# V1.net
KiCad netlist of a schematic drawn in Altium Designer
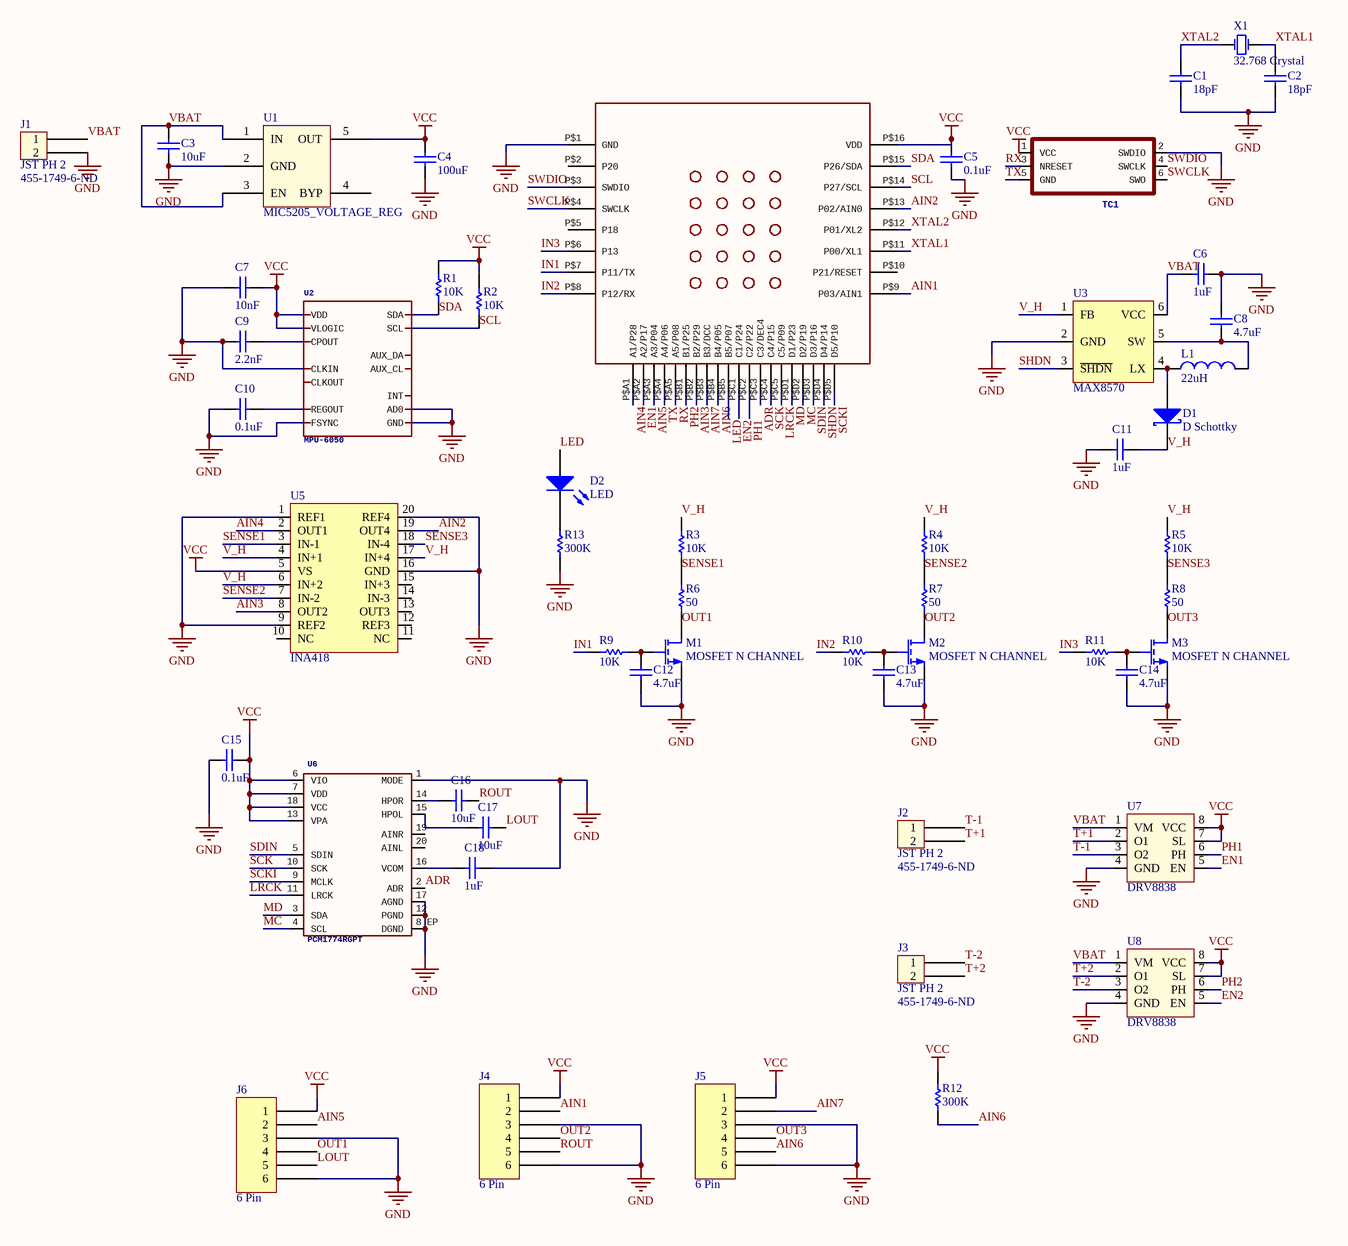
[diagram p0: V1.SchDoc]

(export (version "E")
  (design (tool "Eeschema 10.0.6"))
  (components
    (comp (ref "C1")
      (value "18pF")
      (footprint "0603W")
      (description "SMD Cap 0603")
      (libsource (lib "Artem_Library") (part "Capacitor"))
    )
    (comp (ref "C2")
      (value "18pF")
      (footprint "0603W")
      (description "SMD Cap 0603")
      (libsource (lib "Artem_Library") (part "Capacitor"))
    )
    (comp (ref "C3")
      (value "10uF")
      (footprint "0603W")
      (description "SMD Cap 0603")
      (libsource (lib "Artem_Library") (part "Capacitor"))
    )
    (comp (ref "C4")
      (value "100uF")
      (footprint "0603W")
      (description "SMD Cap 0603")
      (libsource (lib "Artem_Library") (part "Capacitor"))
    )
    (comp (ref "C5")
      (value "0.1uF")
      (footprint "0603W")
      (description "SMD Cap 0603")
      (libsource (lib "Artem_Library") (part "Capacitor"))
    )
    (comp (ref "C6")
      (value "1uF")
      (footprint "0603W")
      (description "SMD Cap 0603")
      (libsource (lib "Artem_Library") (part "Capacitor"))
    )
    (comp (ref "C7")
      (value "10nF")
      (footprint "0603W")
      (description "SMD Cap 0603")
      (libsource (lib "Artem_Library") (part "Capacitor"))
    )
    (comp (ref "C8")
      (value "4.7uF")
      (footprint "0603W")
      (description "SMD Cap 0603")
      (libsource (lib "Artem_Library") (part "Capacitor"))
    )
    (comp (ref "C9")
      (value "2.2nF")
      (footprint "0603W")
      (description "SMD Cap 0603")
      (libsource (lib "Artem_Library") (part "Capacitor"))
    )
    (comp (ref "C10")
      (value "0.1uF")
      (footprint "0603W")
      (description "SMD Cap 0603")
      (libsource (lib "Artem_Library") (part "Capacitor"))
    )
    (comp (ref "C11")
      (value "1uF")
      (footprint "0603W")
      (description "SMD Cap 0603")
      (libsource (lib "Artem_Library") (part "Capacitor"))
    )
    (comp (ref "C12")
      (value "4.7uF")
      (footprint "0603W")
      (description "SMD Cap 0603")
      (libsource (lib "Artem_Library") (part "Capacitor"))
    )
    (comp (ref "C13")
      (value "4.7uF")
      (footprint "0603W")
      (description "SMD Cap 0603")
      (libsource (lib "Artem_Library") (part "Capacitor"))
    )
    (comp (ref "C14")
      (value "4.7uF")
      (footprint "0603W")
      (description "SMD Cap 0603")
      (libsource (lib "Artem_Library") (part "Capacitor"))
    )
    (comp (ref "C15")
      (value "0.1uF")
      (footprint "0603W")
      (description "SMD Cap 0603")
      (libsource (lib "Artem_Library") (part "Capacitor"))
    )
    (comp (ref "C16")
      (value "10uF")
      (footprint "0603W")
      (description "SMD Cap 0603")
      (libsource (lib "Artem_Library") (part "Capacitor"))
    )
    (comp (ref "C17")
      (value "10uF")
      (footprint "0603W")
      (description "SMD Cap 0603")
      (libsource (lib "Artem_Library") (part "Capacitor"))
    )
    (comp (ref "C18")
      (value "1uF")
      (footprint "0603W")
      (description "SMD Cap 0603")
      (libsource (lib "Artem_Library") (part "Capacitor"))
    )
    (comp (ref "D1")
      (value "D Schottky")
      (footprint "0603W")
      (description "Schottky Diode")
      (fields (field (name "PUBLISHER") "Altium Limited"))
      (libsource (lib "Miscellaneous Devices") (part "D Schottky"))
    )
    (comp (ref "D2")
      (value "LED")
      (footprint "0603 LED")
      (description "LED SMD 1206/0603")
      (libsource (lib "Artem_Library") (part "LED"))
    )
    (comp (ref "J1")
      (value "JST PH 2")
      (footprint "JST PH 2")
      (fields (field (name "SUPPLIER PART NUMBER 1") "455-1749-6-ND"))
      (libsource (lib "Artem_Library") (part "JST PH 2"))
    )
    (comp (ref "J2")
      (value "JST PH 2")
      (footprint "JST PH 2")
      (fields (field (name "SUPPLIER PART NUMBER 1") "455-1749-6-ND"))
      (libsource (lib "Artem_Library") (part "JST PH 2"))
    )
    (comp (ref "J3")
      (value "JST PH 2")
      (footprint "JST PH 2")
      (fields (field (name "SUPPLIER PART NUMBER 1") "455-1749-6-ND"))
      (libsource (lib "Artem_Library") (part "JST PH 2"))
    )
    (comp (ref "J4")
      (value "6 Pin")
      (footprint "JST SM06B-SRSS-TB")
      (libsource (lib "Connectors") (part "6 Pin"))
    )
    (comp (ref "J5")
      (value "6 Pin")
      (footprint "JST SM06B-SRSS-TB")
      (libsource (lib "Connectors") (part "6 Pin"))
    )
    (comp (ref "J6")
      (value "6 Pin")
      (footprint "JST SM06B-SRSS-TB")
      (libsource (lib "Connectors") (part "6 Pin"))
    )
    (comp (ref "L1") (value "22uH") (footprint "0603W") (libsource (lib "Artem_Library") (part "Inductor")))
    (comp (ref "M1")
      (value "MOSFET N CHANNEL")
      (footprint "SOT323")
      (fields (field (name "DIGIKEY PART NUMBER") "568-5987-1-ND"))
      (libsource (lib "Artem_Library") (part "MOSFET N CHANNEL"))
    )
    (comp (ref "M2")
      (value "MOSFET N CHANNEL")
      (footprint "SOT323")
      (fields (field (name "DIGIKEY PART NUMBER") "568-5987-1-ND"))
      (libsource (lib "Artem_Library") (part "MOSFET N CHANNEL"))
    )
    (comp (ref "M3")
      (value "MOSFET N CHANNEL")
      (footprint "SOT323")
      (fields (field (name "DIGIKEY PART NUMBER") "568-5987-1-ND"))
      (libsource (lib "Artem_Library") (part "MOSFET N CHANNEL"))
    )
    (comp (ref "R1") (value "10K") (footprint "0603W") (libsource (lib "Artem_Library") (part "Resistor")))
    (comp (ref "R2") (value "10K") (footprint "0603W") (libsource (lib "Artem_Library") (part "Resistor")))
    (comp (ref "R3") (value "10K") (footprint "0603W") (libsource (lib "Artem_Library") (part "Resistor")))
    (comp (ref "R4") (value "10K") (footprint "0603W") (libsource (lib "Artem_Library") (part "Resistor")))
    (comp (ref "R5") (value "10K") (footprint "0603W") (libsource (lib "Artem_Library") (part "Resistor")))
    (comp (ref "R6") (value "50") (footprint "0603W") (libsource (lib "Artem_Library") (part "Resistor")))
    (comp (ref "R7") (value "50") (footprint "0603W") (libsource (lib "Artem_Library") (part "Resistor")))
    (comp (ref "R8") (value "50") (footprint "0603W") (libsource (lib "Artem_Library") (part "Resistor")))
    (comp (ref "R9") (value "10K") (footprint "0603W") (libsource (lib "Artem_Library") (part "Resistor")))
    (comp (ref "R10") (value "10K") (footprint "0603W") (libsource (lib "Artem_Library") (part "Resistor")))
    (comp (ref "R11") (value "10K") (footprint "0603W") (libsource (lib "Artem_Library") (part "Resistor")))
    (comp (ref "R12") (value "300K") (footprint "0603W") (libsource (lib "Artem_Library") (part "Resistor")))
    (comp (ref "R13") (value "300K") (footprint "0603W") (libsource (lib "Artem_Library") (part "Resistor")))
    (comp (ref "TC1")
      (value "~")
      (footprint "TC2030-IDC-NL")
      (libsource (lib "TagConnect") (part "TC2030-IDC-NL"))
    )
    (comp (ref "U1")
      (value "MIC5205_VOLTAGE_REG")
      (footprint "SOT-23-5")
      (description "3.3V LDO SMD")
      (libsource (lib "Artem_Library") (part "MIC5205_VOLTAGE_REG"))
    )
    (comp (ref "U2")
      (value "MPU-6050")
      (footprint "QFN24")
      (fields (field (name "LIBRARYNAME") "invensense"))
      (libsource (lib "invensense") (part "MPU-6050"))
    )
    (comp (ref "U3") (value "MAX8570") (footprint "SOT23-6") (libsource (lib "aby") (part "MAX8570")))
    (comp (ref "U4")
      (value "B3 DCC ,C3 DEC4 for power saving , 10uH , 15nH")
      (footprint "BC832")
      (libsource (lib "BC832") (part "BC832-V1"))
    )
    (comp (ref "U5") (value "INA418") (footprint "TSSOP-20") (libsource (lib "aby") (part "INA418")))
    (comp (ref "U6") (value "PCM1774RGPT") (footprint "QFN20") (libsource (lib "TI") (part "PCM1774RGPT")))
    (comp (ref "U7") (value "DRV8838") (footprint "DRV8838") (libsource (lib "aby") (part "DRV8838")))
    (comp (ref "U8") (value "DRV8838") (footprint "DRV8838") (libsource (lib "aby") (part "DRV8838")))
    (comp (ref "X1")
      (value "32.768 Crystal")
      (footprint "32.768 Crystal")
      (libsource (lib "Artem_Library") (part "32.768 Crystal"))
    )
  )
  (nets
    (net (code "1") (name "/ADR") (class "Default")
      (node (ref "U4") (pin "P$C3") (pinfunction "C3/DEC4_P$C3") (pintype "passive"))
      (node (ref "U6") (pin "2") (pinfunction "ADR_2") (pintype "passive"))
    )
    (net (code "2") (name "/AIN1") (class "Default")
      (node (ref "J4") (pin "2") (pinfunction "2_2") (pintype "passive"))
      (node (ref "U4") (pin "P$9") (pinfunction "P03/AIN1_P$9") (pintype "passive"))
    )
    (net (code "3") (name "/AIN2") (class "Default")
      (node (ref "U4") (pin "P$13") (pinfunction "P02/AIN0_P$13") (pintype "passive"))
      (node (ref "U5") (pin "19") (pinfunction "OUT4_19") (pintype "passive"))
    )
    (net (code "4") (name "/AIN3") (class "Default")
      (node (ref "U4") (pin "P$B2") (pinfunction "B2/P29_P$B2") (pintype "passive"))
      (node (ref "U5") (pin "8") (pinfunction "OUT2_8") (pintype "passive"))
    )
    (net (code "5") (name "/AIN4") (class "Default")
      (node (ref "U4") (pin "P$A1") (pinfunction "A1/P28_P$A1") (pintype "passive"))
      (node (ref "U5") (pin "2") (pinfunction "OUT1_2") (pintype "passive"))
    )
    (net (code "6") (name "/AIN5") (class "Default")
      (node (ref "J6") (pin "2") (pinfunction "2_2") (pintype "passive"))
      (node (ref "U4") (pin "P$A3") (pinfunction "A3/P04_P$A3") (pintype "passive"))
    )
    (net (code "7") (name "/AIN6") (class "Default")
      (node (ref "J5") (pin "5") (pinfunction "5_5") (pintype "passive"))
      (node (ref "R12") (pin "1") (pinfunction "1_1") (pintype "passive"))
      (node (ref "U4") (pin "P$B4") (pinfunction "B4/P05_P$B4") (pintype "passive"))
    )
    (net (code "8") (name "/AIN7") (class "Default")
      (node (ref "J5") (pin "2") (pinfunction "2_2") (pintype "passive"))
      (node (ref "U4") (pin "P$B3") (pinfunction "B3/DCC_P$B3") (pintype "passive"))
    )
    (net (code "9") (name "/EN1") (class "Default")
      (node (ref "U4") (pin "P$A2") (pinfunction "A2/P17_P$A2") (pintype "passive"))
      (node (ref "U7") (pin "5") (pinfunction "EN_5") (pintype "passive"))
    )
    (net (code "10") (name "/EN2") (class "Default")
      (node (ref "U4") (pin "P$C1") (pinfunction "C1/P24_P$C1") (pintype "passive"))
      (node (ref "U8") (pin "5") (pinfunction "EN_5") (pintype "passive"))
    )
    (net (code "11") (name "/IN1") (class "Default")
      (node (ref "R9") (pin "1") (pinfunction "1_1") (pintype "passive"))
      (node (ref "U4") (pin "P$7") (pinfunction "P11/TX_P$7") (pintype "passive"))
    )
    (net (code "12") (name "/IN2") (class "Default")
      (node (ref "R10") (pin "1") (pinfunction "1_1") (pintype "passive"))
      (node (ref "U4") (pin "P$8") (pinfunction "P12/RX_P$8") (pintype "passive"))
    )
    (net (code "13") (name "/IN3") (class "Default")
      (node (ref "R11") (pin "1") (pinfunction "1_1") (pintype "passive"))
      (node (ref "U4") (pin "P$6") (pinfunction "P13_P$6") (pintype "passive"))
    )
    (net (code "14") (name "/LED") (class "Default")
      (node (ref "D2") (pin "1") (pinfunction "A_1") (pintype "passive"))
      (node (ref "U4") (pin "P$B5") (pinfunction "B5/P07_P$B5") (pintype "passive"))
    )
    (net (code "15") (name "/LOUT") (class "Default")
      (node (ref "C17") (pin "1") (pinfunction "1_1") (pintype "passive"))
      (node (ref "J6") (pin "5") (pinfunction "5_5") (pintype "passive"))
    )
    (net (code "16") (name "/LRCK") (class "Default")
      (node (ref "U4") (pin "P$C5") (pinfunction "C5/P09_P$C5") (pintype "passive"))
      (node (ref "U6") (pin "11") (pinfunction "LRCK_11") (pintype "passive"))
    )
    (net (code "17") (name "/MC") (class "Default")
      (node (ref "U4") (pin "P$D2") (pinfunction "D2/P19_P$D2") (pintype "passive"))
      (node (ref "U6") (pin "4") (pinfunction "SCL_4") (pintype "passive"))
    )
    (net (code "18") (name "/MD") (class "Default")
      (node (ref "U4") (pin "P$D1") (pinfunction "D1/P23_P$D1") (pintype "passive"))
      (node (ref "U6") (pin "3") (pinfunction "SDA_3") (pintype "passive"))
    )
    (net (code "19") (name "/OUT1") (class "Default")
      (node (ref "J6") (pin "4") (pinfunction "4_4") (pintype "passive"))
      (node (ref "M1") (pin "3") (pinfunction "D_3") (pintype "passive"))
      (node (ref "R6") (pin "1") (pinfunction "1_1") (pintype "passive"))
    )
    (net (code "20") (name "/OUT2") (class "Default")
      (node (ref "J4") (pin "4") (pinfunction "4_4") (pintype "passive"))
      (node (ref "M2") (pin "3") (pinfunction "D_3") (pintype "passive"))
      (node (ref "R7") (pin "1") (pinfunction "1_1") (pintype "passive"))
    )
    (net (code "21") (name "/OUT3") (class "Default")
      (node (ref "J5") (pin "4") (pinfunction "4_4") (pintype "passive"))
      (node (ref "M3") (pin "3") (pinfunction "D_3") (pintype "passive"))
      (node (ref "R8") (pin "1") (pinfunction "1_1") (pintype "passive"))
    )
    (net (code "22") (name "/PH1") (class "Default")
      (node (ref "U4") (pin "P$C2") (pinfunction "C2/P22_P$C2") (pintype "passive"))
      (node (ref "U7") (pin "6") (pinfunction "PH_6") (pintype "passive"))
    )
    (net (code "23") (name "/PH2") (class "Default")
      (node (ref "U4") (pin "P$B1") (pinfunction "B1/P25_P$B1") (pintype "passive"))
      (node (ref "U8") (pin "6") (pinfunction "PH_6") (pintype "passive"))
    )
    (net (code "24") (name "/ROUT") (class "Default")
      (node (ref "C16") (pin "1") (pinfunction "1_1") (pintype "passive"))
      (node (ref "J4") (pin "5") (pinfunction "5_5") (pintype "passive"))
    )
    (net (code "25") (name "/RX") (class "Default")
      (node (ref "TC1") (pin "3") (pinfunction "NRESET_3") (pintype "passive"))
      (node (ref "U4") (pin "P$A5") (pinfunction "A5/P08_P$A5") (pintype "passive"))
    )
    (net (code "26") (name "/SCK") (class "Default")
      (node (ref "U4") (pin "P$C4") (pinfunction "C4/P15_P$C4") (pintype "passive"))
      (node (ref "U6") (pin "10") (pinfunction "SCK_10") (pintype "passive"))
    )
    (net (code "27") (name "/SCKI") (class "Default")
      (node (ref "U4") (pin "P$D5") (pinfunction "D5/P10_P$D5") (pintype "passive"))
      (node (ref "U6") (pin "9") (pinfunction "MCLK_9") (pintype "passive"))
    )
    (net (code "28") (name "/SCL") (class "Default")
      (node (ref "R2") (pin "2") (pinfunction "2_2") (pintype "passive"))
      (node (ref "U2") (pin "23") (pinfunction "SCL_23") (pintype "passive"))
      (node (ref "U4") (pin "P$14") (pinfunction "P27/SCL_P$14") (pintype "passive"))
    )
    (net (code "29") (name "/SDA") (class "Default")
      (node (ref "R1") (pin "2") (pinfunction "2_2") (pintype "passive"))
      (node (ref "U2") (pin "24") (pinfunction "SDA_24") (pintype "passive"))
      (node (ref "U4") (pin "P$15") (pinfunction "P26/SDA_P$15") (pintype "passive"))
    )
    (net (code "30") (name "/SDIN") (class "Default")
      (node (ref "U4") (pin "P$D3") (pinfunction "D3/P16_P$D3") (pintype "passive"))
      (node (ref "U6") (pin "5") (pinfunction "SDIN_5") (pintype "passive"))
    )
    (net (code "31") (name "/SENSE1") (class "Default")
      (node (ref "R3") (pin "1") (pinfunction "1_1") (pintype "passive"))
      (node (ref "R6") (pin "2") (pinfunction "2_2") (pintype "passive"))
      (node (ref "U5") (pin "3") (pinfunction "IN-1_3") (pintype "passive"))
    )
    (net (code "32") (name "/SENSE2") (class "Default")
      (node (ref "R4") (pin "1") (pinfunction "1_1") (pintype "passive"))
      (node (ref "R7") (pin "2") (pinfunction "2_2") (pintype "passive"))
      (node (ref "U5") (pin "7") (pinfunction "IN-2_7") (pintype "passive"))
    )
    (net (code "33") (name "/SENSE3") (class "Default")
      (node (ref "R5") (pin "1") (pinfunction "1_1") (pintype "passive"))
      (node (ref "R8") (pin "2") (pinfunction "2_2") (pintype "passive"))
      (node (ref "U5") (pin "18") (pinfunction "IN-4_18") (pintype "passive"))
    )
    (net (code "34") (name "/SHDN") (class "Default")
      (node (ref "U3") (pin "3") (pinfunction "~{SHDN}_3") (pintype "passive"))
      (node (ref "U4") (pin "P$D4") (pinfunction "D4/P14_P$D4") (pintype "passive"))
    )
    (net (code "35") (name "/SWCLK") (class "Default")
      (node (ref "TC1") (pin "6") (pinfunction "SWO_6") (pintype "passive"))
      (node (ref "U4") (pin "P$4") (pinfunction "SWCLK_P$4") (pintype "passive"))
    )
    (net (code "36") (name "/SWDIO") (class "Default")
      (node (ref "TC1") (pin "4") (pinfunction "SWCLK_4") (pintype "passive"))
      (node (ref "U4") (pin "P$3") (pinfunction "SWDIO_P$3") (pintype "passive"))
    )
    (net (code "37") (name "/T+1") (class "Default")
      (node (ref "J2") (pin "2") (pinfunction "2_2") (pintype "passive"))
      (node (ref "U7") (pin "2") (pinfunction "O1_2") (pintype "passive"))
    )
    (net (code "38") (name "/T+2") (class "Default")
      (node (ref "J3") (pin "2") (pinfunction "2_2") (pintype "passive"))
      (node (ref "U8") (pin "2") (pinfunction "O1_2") (pintype "passive"))
    )
    (net (code "39") (name "/T-1") (class "Default")
      (node (ref "J2") (pin "1") (pinfunction "1_1") (pintype "passive"))
      (node (ref "U7") (pin "3") (pinfunction "O2_3") (pintype "passive"))
    )
    (net (code "40") (name "/T-2") (class "Default")
      (node (ref "J3") (pin "1") (pinfunction "1_1") (pintype "passive"))
      (node (ref "U8") (pin "3") (pinfunction "O2_3") (pintype "passive"))
    )
    (net (code "41") (name "/TX") (class "Default")
      (node (ref "TC1") (pin "5") (pinfunction "GND_5") (pintype "passive"))
      (node (ref "U4") (pin "P$A4") (pinfunction "A4/P06_P$A4") (pintype "passive"))
    )
    (net (code "42") (name "/VBAT") (class "Default")
      (node (ref "C3") (pin "2") (pinfunction "2_2") (pintype "passive"))
      (node (ref "C6") (pin "2") (pinfunction "2_2") (pintype "passive"))
      (node (ref "J1") (pin "1") (pinfunction "1_1") (pintype "passive"))
      (node (ref "U1") (pin "1") (pinfunction "IN_1") (pintype "passive"))
      (node (ref "U1") (pin "3") (pinfunction "EN_3") (pintype "passive"))
      (node (ref "U3") (pin "6") (pinfunction "VCC_6") (pintype "passive"))
      (node (ref "U7") (pin "1") (pinfunction "VM_1") (pintype "passive"))
      (node (ref "U8") (pin "1") (pinfunction "VM_1") (pintype "passive"))
    )
    (net (code "43") (name "/V_H") (class "Default")
      (node (ref "C11") (pin "1") (pinfunction "1_1") (pintype "passive"))
      (node (ref "D1") (pin "2") (pinfunction "K_2") (pintype "passive"))
      (node (ref "R3") (pin "2") (pinfunction "2_2") (pintype "passive"))
      (node (ref "R4") (pin "2") (pinfunction "2_2") (pintype "passive"))
      (node (ref "R5") (pin "2") (pinfunction "2_2") (pintype "passive"))
      (node (ref "U3") (pin "1") (pinfunction "FB_1") (pintype "passive"))
      (node (ref "U5") (pin "17") (pinfunction "IN+4_17") (pintype "passive"))
      (node (ref "U5") (pin "4") (pinfunction "IN+1_4") (pintype "passive"))
      (node (ref "U5") (pin "6") (pinfunction "IN+2_6") (pintype "passive"))
    )
    (net (code "44") (name "/XTAL1") (class "Default")
      (node (ref "C2") (pin "2") (pinfunction "2_2") (pintype "passive"))
      (node (ref "U4") (pin "P$11") (pinfunction "P00/XL1_P$11") (pintype "passive"))
      (node (ref "X1") (pin "2") (pinfunction "2_2") (pintype "passive"))
    )
    (net (code "45") (name "/XTAL2") (class "Default")
      (node (ref "C1") (pin "1") (pinfunction "1_1") (pintype "passive"))
      (node (ref "U4") (pin "P$12") (pinfunction "P01/XL2_P$12") (pintype "passive"))
      (node (ref "X1") (pin "1") (pinfunction "1_1") (pintype "passive"))
    )
    (net (code "46") (name "GND") (class "Default")
      (node (ref "C1") (pin "2") (pinfunction "2_2") (pintype "passive"))
      (node (ref "C10") (pin "2") (pinfunction "2_2") (pintype "passive"))
      (node (ref "C11") (pin "2") (pinfunction "2_2") (pintype "passive"))
      (node (ref "C12") (pin "2") (pinfunction "2_2") (pintype "passive"))
      (node (ref "C13") (pin "2") (pinfunction "2_2") (pintype "passive"))
      (node (ref "C14") (pin "2") (pinfunction "2_2") (pintype "passive"))
      (node (ref "C15") (pin "2") (pinfunction "2_2") (pintype "passive"))
      (node (ref "C18") (pin "1") (pinfunction "1_1") (pintype "passive"))
      (node (ref "C2") (pin "1") (pinfunction "1_1") (pintype "passive"))
      (node (ref "C3") (pin "1") (pinfunction "1_1") (pintype "passive"))
      (node (ref "C4") (pin "1") (pinfunction "1_1") (pintype "passive"))
      (node (ref "C5") (pin "1") (pinfunction "1_1") (pintype "passive"))
      (node (ref "C6") (pin "1") (pinfunction "1_1") (pintype "passive"))
      (node (ref "C7") (pin "2") (pinfunction "2_2") (pintype "passive"))
      (node (ref "C8") (pin "1") (pinfunction "1_1") (pintype "passive"))
      (node (ref "C9") (pin "2") (pinfunction "2_2") (pintype "passive"))
      (node (ref "J1") (pin "2") (pinfunction "2_2") (pintype "passive"))
      (node (ref "J4") (pin "3") (pinfunction "3_3") (pintype "passive"))
      (node (ref "J4") (pin "6") (pinfunction "6_6") (pintype "passive"))
      (node (ref "J5") (pin "3") (pinfunction "3_3") (pintype "passive"))
      (node (ref "J5") (pin "6") (pinfunction "6_6") (pintype "passive"))
      (node (ref "J6") (pin "3") (pinfunction "3_3") (pintype "passive"))
      (node (ref "J6") (pin "6") (pinfunction "6_6") (pintype "passive"))
      (node (ref "M1") (pin "2") (pinfunction "S_2") (pintype "passive"))
      (node (ref "M2") (pin "2") (pinfunction "S_2") (pintype "passive"))
      (node (ref "M3") (pin "2") (pinfunction "S_2") (pintype "passive"))
      (node (ref "R13") (pin "1") (pinfunction "1_1") (pintype "passive"))
      (node (ref "TC1") (pin "2") (pinfunction "SWDIO_2") (pintype "passive"))
      (node (ref "U1") (pin "2") (pinfunction "GND_2") (pintype "passive"))
      (node (ref "U2") (pin "1") (pinfunction "CLKIN_1") (pintype "passive"))
      (node (ref "U2") (pin "11") (pinfunction "FSYNC_11") (pintype "passive"))
      (node (ref "U2") (pin "18") (pinfunction "GND_18") (pintype "passive"))
      (node (ref "U2") (pin "9") (pinfunction "AD0_9") (pintype "passive"))
      (node (ref "U3") (pin "2") (pinfunction "GND_2") (pintype "passive"))
      (node (ref "U4") (pin "P$1") (pinfunction "GND_P$1") (pintype "passive"))
      (node (ref "U5") (pin "1") (pinfunction "REF1_1") (pintype "passive"))
      (node (ref "U5") (pin "16") (pinfunction "GND_16") (pintype "passive"))
      (node (ref "U5") (pin "20") (pinfunction "REF4_20") (pintype "passive"))
      (node (ref "U5") (pin "9") (pinfunction "REF2_9") (pintype "passive"))
      (node (ref "U6") (pin "1") (pinfunction "MODE_1") (pintype "passive"))
      (node (ref "U6") (pin "12") (pinfunction "PGND_12") (pintype "passive"))
      (node (ref "U6") (pin "17") (pinfunction "AGND_17") (pintype "passive"))
      (node (ref "U6") (pin "8_EP") (pinfunction "DGND_8_EP") (pintype "passive"))
      (node (ref "U7") (pin "4") (pinfunction "GND_4") (pintype "passive"))
      (node (ref "U8") (pin "4") (pinfunction "GND_4") (pintype "passive"))
    )
    (net (code "47") (name "Net-(D1-A)") (class "Default")
      (node (ref "D1") (pin "1") (pinfunction "A_1") (pintype "passive"))
      (node (ref "L1") (pin "1") (pinfunction "1_1") (pintype "passive"))
      (node (ref "U3") (pin "4") (pinfunction "LX_4") (pintype "passive"))
    )
    (net (code "48") (name "Net-(D2-K)") (class "Default")
      (node (ref "D2") (pin "2") (pinfunction "K_2") (pintype "passive"))
      (node (ref "R13") (pin "2") (pinfunction "2_2") (pintype "passive"))
    )
    (net (code "49") (name "Net-(M1-G)") (class "Default")
      (node (ref "C12") (pin "1") (pinfunction "1_1") (pintype "passive"))
      (node (ref "M1") (pin "1") (pinfunction "G_1") (pintype "passive"))
      (node (ref "R9") (pin "2") (pinfunction "2_2") (pintype "passive"))
    )
    (net (code "50") (name "Net-(M2-G)") (class "Default")
      (node (ref "C13") (pin "1") (pinfunction "1_1") (pintype "passive"))
      (node (ref "M2") (pin "1") (pinfunction "G_1") (pintype "passive"))
      (node (ref "R10") (pin "2") (pinfunction "2_2") (pintype "passive"))
    )
    (net (code "51") (name "Net-(M3-G)") (class "Default")
      (node (ref "C14") (pin "1") (pinfunction "1_1") (pintype "passive"))
      (node (ref "M3") (pin "1") (pinfunction "G_1") (pintype "passive"))
      (node (ref "R11") (pin "2") (pinfunction "2_2") (pintype "passive"))
    )
    (net (code "52") (name "Net-(U2-CPOUT)") (class "Default")
      (node (ref "C9") (pin "1") (pinfunction "1_1") (pintype "passive"))
      (node (ref "U2") (pin "20") (pinfunction "CPOUT_20") (pintype "passive"))
    )
    (net (code "53") (name "Net-(U2-REGOUT)") (class "Default")
      (node (ref "C10") (pin "1") (pinfunction "1_1") (pintype "passive"))
      (node (ref "U2") (pin "10") (pinfunction "REGOUT_10") (pintype "passive"))
    )
    (net (code "54") (name "Net-(U3-SW)") (class "Default")
      (node (ref "C8") (pin "2") (pinfunction "2_2") (pintype "passive"))
      (node (ref "L1") (pin "2") (pinfunction "2_2") (pintype "passive"))
      (node (ref "U3") (pin "5") (pinfunction "SW_5") (pintype "passive"))
    )
    (net (code "55") (name "Net-(U6-HPOL)") (class "Default")
      (node (ref "C17") (pin "2") (pinfunction "2_2") (pintype "passive"))
      (node (ref "U6") (pin "15") (pinfunction "HPOL_15") (pintype "passive"))
    )
    (net (code "56") (name "Net-(U6-HPOR)") (class "Default")
      (node (ref "C16") (pin "2") (pinfunction "2_2") (pintype "passive"))
      (node (ref "U6") (pin "14") (pinfunction "HPOR_14") (pintype "passive"))
    )
    (net (code "57") (name "Net-(U6-VCOM)") (class "Default")
      (node (ref "C18") (pin "2") (pinfunction "2_2") (pintype "passive"))
      (node (ref "U6") (pin "16") (pinfunction "VCOM_16") (pintype "passive"))
    )
    (net (code "58") (name "VCC") (class "Default")
      (node (ref "C15") (pin "1") (pinfunction "1_1") (pintype "passive"))
      (node (ref "C4") (pin "2") (pinfunction "2_2") (pintype "passive"))
      (node (ref "C5") (pin "2") (pinfunction "2_2") (pintype "passive"))
      (node (ref "C7") (pin "1") (pinfunction "1_1") (pintype "passive"))
      (node (ref "J4") (pin "1") (pinfunction "1_1") (pintype "passive"))
      (node (ref "J5") (pin "1") (pinfunction "1_1") (pintype "passive"))
      (node (ref "J6") (pin "1") (pinfunction "1_1") (pintype "passive"))
      (node (ref "R1") (pin "1") (pinfunction "1_1") (pintype "passive"))
      (node (ref "R12") (pin "2") (pinfunction "2_2") (pintype "passive"))
      (node (ref "R2") (pin "1") (pinfunction "1_1") (pintype "passive"))
      (node (ref "TC1") (pin "1") (pinfunction "VCC_1") (pintype "passive"))
      (node (ref "U1") (pin "5") (pinfunction "OUT_5") (pintype "passive"))
      (node (ref "U2") (pin "13") (pinfunction "VDD_13") (pintype "passive"))
      (node (ref "U2") (pin "8") (pinfunction "VLOGIC_8") (pintype "passive"))
      (node (ref "U4") (pin "P$16") (pinfunction "VDD_P$16") (pintype "passive"))
      (node (ref "U5") (pin "5") (pinfunction "VS_5") (pintype "passive"))
      (node (ref "U6") (pin "13") (pinfunction "VPA_13") (pintype "passive"))
      (node (ref "U6") (pin "18") (pinfunction "VCC_18") (pintype "passive"))
      (node (ref "U6") (pin "6") (pinfunction "VIO_6") (pintype "passive"))
      (node (ref "U6") (pin "7") (pinfunction "VDD_7") (pintype "passive"))
      (node (ref "U7") (pin "7") (pinfunction "SL_7") (pintype "passive"))
      (node (ref "U7") (pin "8") (pinfunction "VCC_8") (pintype "passive"))
      (node (ref "U8") (pin "7") (pinfunction "SL_7") (pintype "passive"))
      (node (ref "U8") (pin "8") (pinfunction "VCC_8") (pintype "passive"))
    )
    (net (code "59") (name "unconnected-(U1-BYP-Pad4)") (class "Default")
      (node (ref "U1") (pin "4") (pinfunction "BYP_4") (pintype "passive"))
    )
    (net (code "60") (name "unconnected-(U2-AUX_CL-Pad7)") (class "Default")
      (node (ref "U2") (pin "7") (pinfunction "AUX_CL_7") (pintype "passive"))
    )
    (net (code "61") (name "unconnected-(U2-AUX_DA-Pad6)") (class "Default")
      (node (ref "U2") (pin "6") (pinfunction "AUX_DA_6") (pintype "passive"))
    )
    (net (code "62") (name "unconnected-(U2-CLKOUT-Pad22)") (class "Default")
      (node (ref "U2") (pin "22") (pinfunction "CLKOUT_22") (pintype "passive"))
    )
    (net (code "63") (name "unconnected-(U2-INT-Pad12)") (class "Default")
      (node (ref "U2") (pin "12") (pinfunction "INT_12") (pintype "passive"))
    )
    (net (code "64") (name "unconnected-(U4-P18-PadP$5)") (class "Default")
      (node (ref "U4") (pin "P$5") (pinfunction "P18_P$5") (pintype "passive"))
    )
    (net (code "65") (name "unconnected-(U4-P20-PadP$2)") (class "Default")
      (node (ref "U4") (pin "P$2") (pinfunction "P20_P$2") (pintype "passive"))
    )
    (net (code "66") (name "unconnected-(U4-P21{slash}RESET-PadP$10)") (class "Default")
      (node (ref "U4") (pin "P$10") (pinfunction "P21/RESET_P$10") (pintype "passive"))
    )
    (net (code "67") (name "unconnected-(U5-IN+3-Pad15)") (class "Default")
      (node (ref "U5") (pin "15") (pinfunction "IN+3_15") (pintype "passive"))
    )
    (net (code "68") (name "unconnected-(U5-IN-3-Pad14)") (class "Default")
      (node (ref "U5") (pin "14") (pinfunction "IN-3_14") (pintype "passive"))
    )
    (net (code "69") (name "unconnected-(U5-NC-Pad10)") (class "Default")
      (node (ref "U5") (pin "10") (pinfunction "NC_10") (pintype "passive"))
    )
    (net (code "70") (name "unconnected-(U5-NC-Pad11)") (class "Default")
      (node (ref "U5") (pin "11") (pinfunction "NC_11") (pintype "passive"))
    )
    (net (code "71") (name "unconnected-(U5-OUT3-Pad13)") (class "Default")
      (node (ref "U5") (pin "13") (pinfunction "OUT3_13") (pintype "passive"))
    )
    (net (code "72") (name "unconnected-(U5-REF3-Pad12)") (class "Default")
      (node (ref "U5") (pin "12") (pinfunction "REF3_12") (pintype "passive"))
    )
    (net (code "73") (name "unconnected-(U6-AINL-Pad20)") (class "Default")
      (node (ref "U6") (pin "20") (pinfunction "AINL_20") (pintype "passive"))
    )
    (net (code "74") (name "unconnected-(U6-AINR-Pad19)") (class "Default")
      (node (ref "U6") (pin "19") (pinfunction "AINR_19") (pintype "passive"))
    )
  )
)
